# wifi-bt.net
KiCad netlist of a schematic drawn in Altium Designer
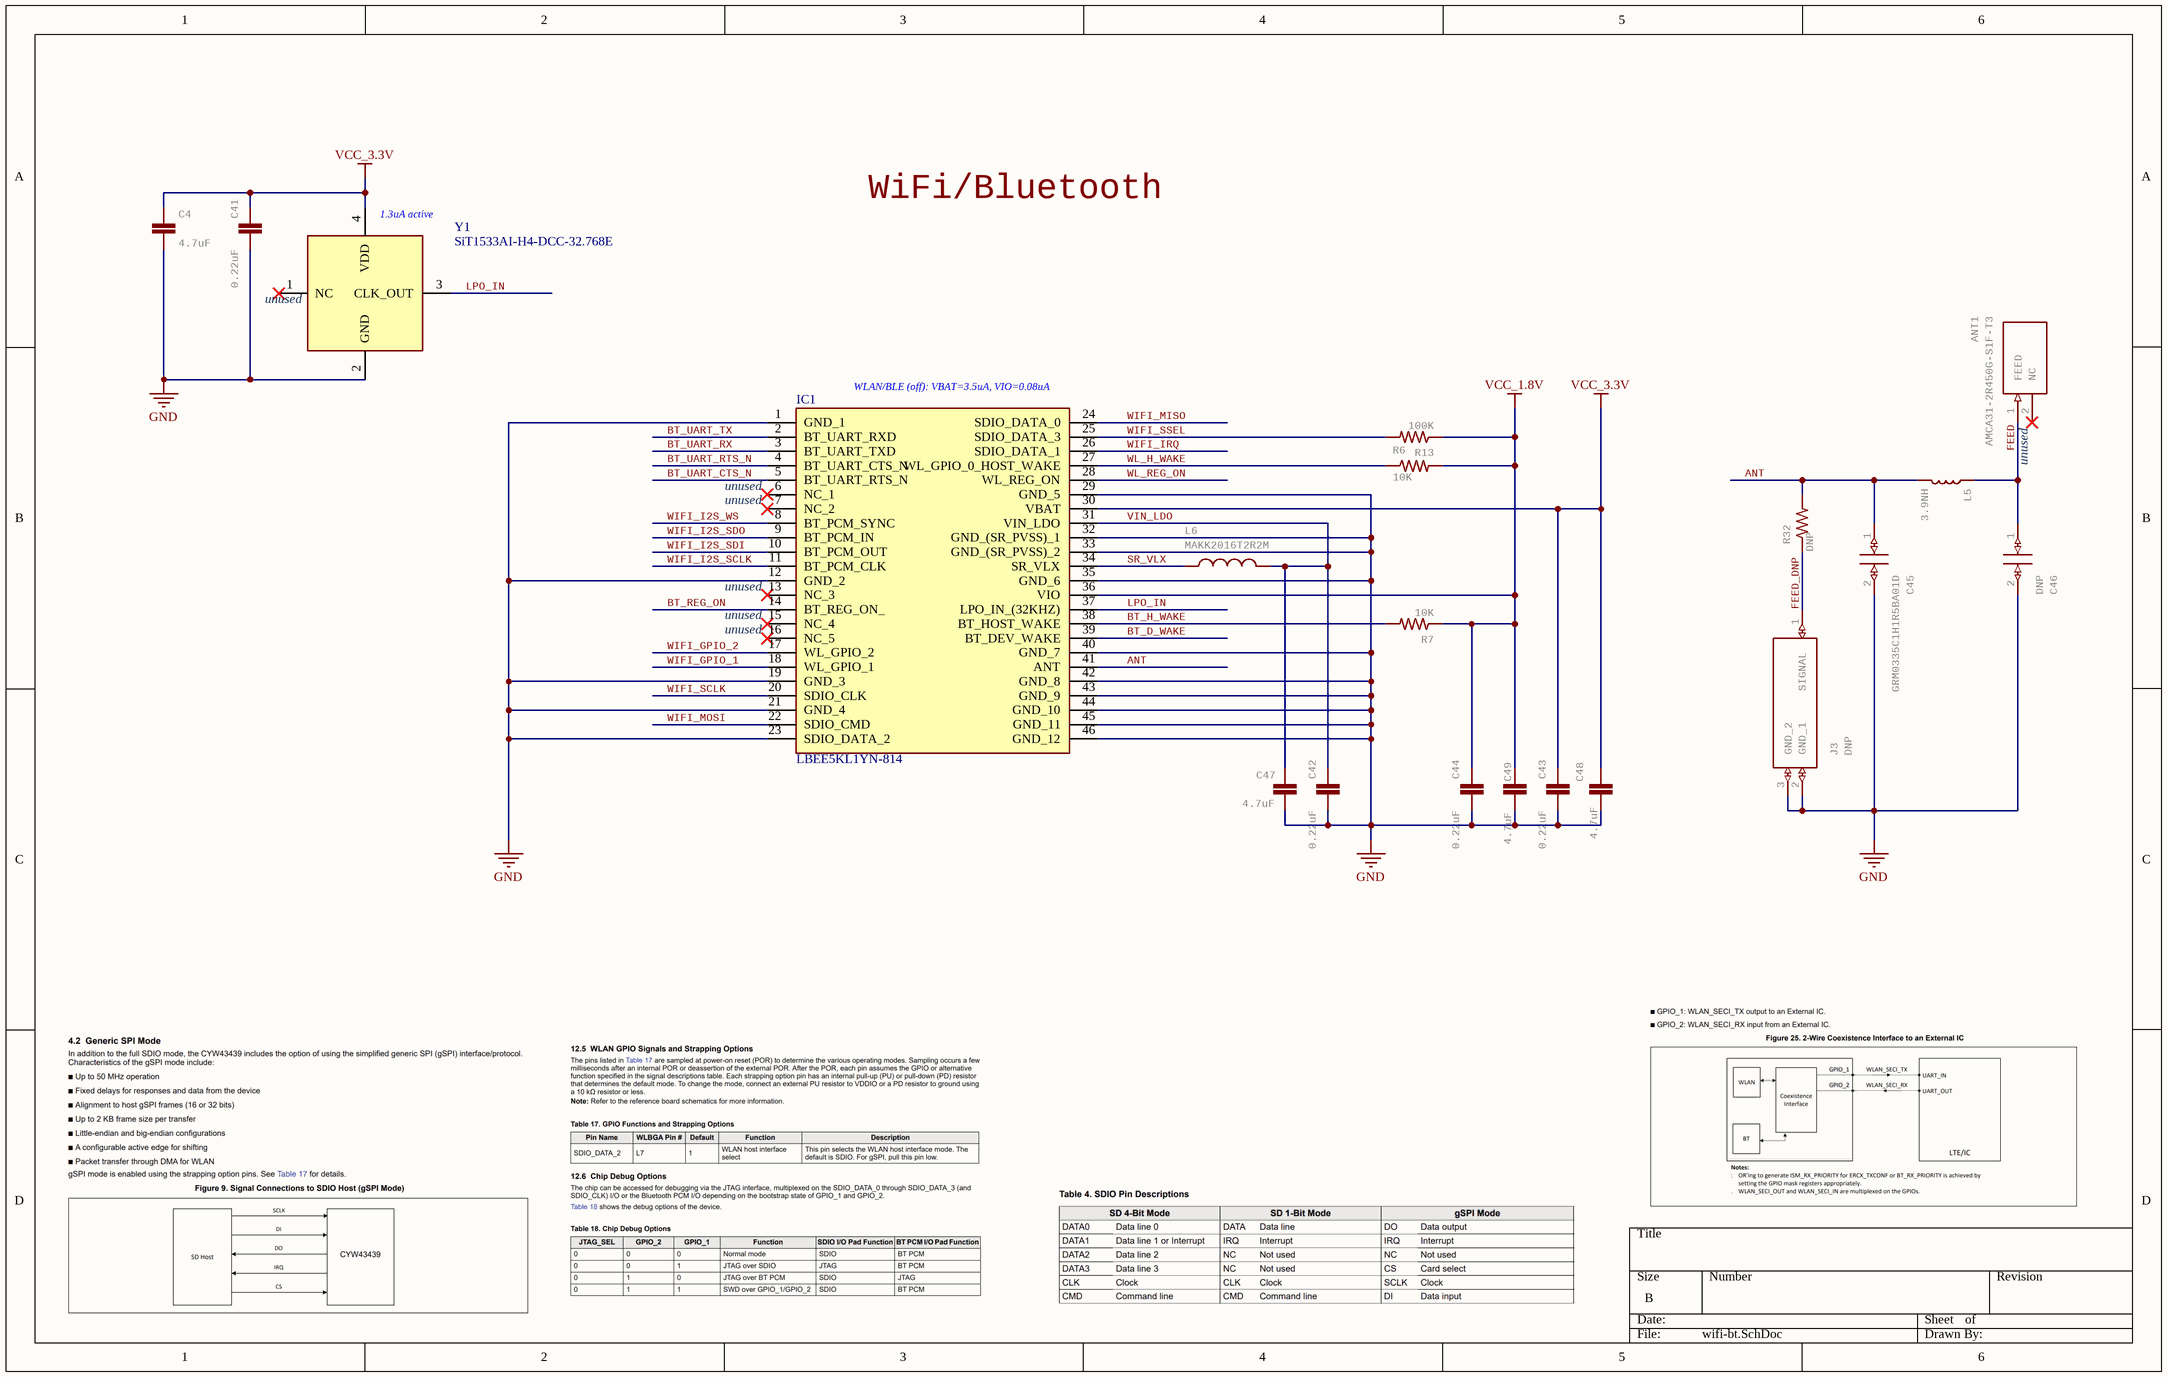
[diagram p0: wifi-bt.SchDoc]

(export (version "E")
  (design (tool "Eeschema 10.0.6"))
  (components
    (comp (ref "ANT1")
      (value "AMCA31-2R450G-S1F-T3")
      (footprint "ANTC3216X140N")
      (description "ABRACON - AMCA31-2R450G-S1F-T3 - ANTENNA, CHIP, 2.45GHZ, 50 OHM, 1206   Source:  Datasheet")
      (fields (field (name "MOUSER_PART_NUMBER") "815-CA312R450GS1FT3"))
      (libsource (lib "openmv-ae3") (part "AMCA31-2R450G-S1F-T3"))
    )
    (comp (ref "C4")
      (value "4.7uF")
      (footprint "0402-CAP")
      (description "CapacitorStandard 0603 ceramic capacitor, and 0.1\" leaded capacitor.")
      (fields (field (name "MPN") "JMK105BBJ475MV-F") (field (name "LIBRARYNAME") "sfe"))
      (libsource (lib "openmv-ae3") (part "CAP0402-CAP"))
    )
    (comp (ref "C41")
      (value "0.22uF")
      (footprint "C0201")
      (description "CAPACITOR, European symbol")
      (fields (field (name "MPN") "GRM033R60J224ME15D"))
      (libsource (lib "openmv-ae3") (part "C-EUC0201"))
    )
    (comp (ref "C42")
      (value "0.22uF")
      (footprint "C0201")
      (description "CAPACITOR, European symbol")
      (fields (field (name "MPN") "GRM033R60J224ME15D"))
      (libsource (lib "openmv-ae3") (part "C-EUC0201"))
    )
    (comp (ref "C43")
      (value "0.22uF")
      (footprint "C0201")
      (description "CAPACITOR, European symbol")
      (fields (field (name "MPN") "GRM033R60J224ME15D"))
      (libsource (lib "openmv-ae3") (part "C-EUC0201"))
    )
    (comp (ref "C44")
      (value "0.22uF")
      (footprint "C0201")
      (description "CAPACITOR, European symbol")
      (fields (field (name "MPN") "GRM033R60J224ME15D"))
      (libsource (lib "openmv-ae3") (part "C-EUC0201"))
    )
    (comp (ref "C45")
      (value "GRM0335C1H1R5BA01D")
      (footprint "CAPC0603X33N")
      (description "Chip Capacitor value 1R5   Source:  Datasheet")
      (fields (field (name "MOUSER_PART_NUMBER") "81-GRM0335C1H1R5BA1D"))
      (libsource (lib "openmv-ae3") (part "GRM0335C1H1R5BA01D"))
    )
    (comp (ref "C46")
      (value "DNP")
      (footprint "C0201-NO-3D")
      (description "Chip Capacitor value 1R5   Source:  Datasheet")
      (fields
        (field (name "MANUFACTURER_PART_NUMBER") "GRM0335C1H1R5BA01D")
        (field (name "MOUSER_PART_NUMBER") "81-GRM0335C1H1R5BA1D")
      )
      (libsource (lib "openmv-ae3") (part "GRM0335C1H1R5BA01D"))
    )
    (comp (ref "C47")
      (value "4.7uF")
      (footprint "0402-CAP")
      (description "CapacitorStandard 0603 ceramic capacitor, and 0.1\" leaded capacitor.")
      (fields (field (name "MPN") "JMK105BBJ475MV-F") (field (name "LIBRARYNAME") "sfe"))
      (libsource (lib "openmv-ae3") (part "CAP0402-CAP"))
    )
    (comp (ref "C48")
      (value "4.7uF")
      (footprint "0402-CAP")
      (description "CapacitorStandard 0603 ceramic capacitor, and 0.1\" leaded capacitor.")
      (fields (field (name "MPN") "JMK105BBJ475MV-F") (field (name "LIBRARYNAME") "sfe"))
      (libsource (lib "openmv-ae3") (part "CAP0402-CAP"))
    )
    (comp (ref "C49")
      (value "4.7uF")
      (footprint "0402-CAP")
      (description "CapacitorStandard 0603 ceramic capacitor, and 0.1\" leaded capacitor.")
      (fields (field (name "MPN") "JMK105BBJ475MV-F") (field (name "LIBRARYNAME") "sfe"))
      (libsource (lib "openmv-ae3") (part "CAP0402-CAP"))
    )
    (comp (ref "IC1")
      (value "LBEE5KL1YN-814")
      (footprint "SamacSys:LBEE5KL1YN814")
      (description "Integrated Circuit")
      (fields (field (name "MOUSER PART NUMBER") "81-LBEE5KL1YN-814"))
      (libsource (lib "openmv-ae3") (part "LBEE5KL1YN-814"))
    )
    (comp (ref "J3")
      (value "DNP")
      (footprint "23370191-NO-3D")
      (description "RF Connectors / Coaxial Connectors MicroCoax receptacle UMCC Gen 1   Source:  Datasheet")
      (fields
        (field (name "MANUFACTURER_PART_NUMBER") "2337019-1")
        (field (name "MOUSER_PART_NUMBER") "571-2337019-1")
      )
      (libsource (lib "openmv-ae3") (part "2337019-1"))
    )
    (comp (ref "L5")
      (value "3.9NH")
      (footprint "0402")
      (fields (field (name "MPN") "L-07C3N9SV6T") (field (name "LIBRARYNAME") "SparkFun-Coils"))
      (libsource (lib "openmv-ae3") (part "INDUCTOR-0402-3.9NH"))
    )
    (comp (ref "L6")
      (value "MAKK2016T2R2M")
      (footprint "INDC2016X100N")
      (description "INDUCTOR, METAL CORE Check availability")
      (fields (field (name "MF") "Taiyo Yuden"))
      (libsource (lib "openmv-ae3") (part "MAKK2016T2R2M"))
    )
    (comp (ref "R6")
      (value "10K")
      (footprint "R0201")
      (fields (field (name "MPN") "RMCF0201FT10K0") (field (name "LIBRARYNAME") "sfe"))
      (libsource (lib "openmv-ae3") (part "RESISTOR0402-RES"))
    )
    (comp (ref "R7")
      (value "10K")
      (footprint "R0201")
      (fields (field (name "MPN") "RMCF0201FT10K0") (field (name "LIBRARYNAME") "sfe"))
      (libsource (lib "openmv-ae3") (part "RESISTOR0402-RES"))
    )
    (comp (ref "R13")
      (value "100K")
      (footprint "R0201")
      (fields (field (name "MPN") "RMCF0201FT100K") (field (name "LIBRARYNAME") "sfe"))
      (libsource (lib "openmv-ae3") (part "RESISTOR0402-RES"))
    )
    (comp (ref "R32")
      (value "DNP")
      (footprint "0402-RES")
      (description "Resistor")
      (fields (field (name "LIBRARYNAME") "sfe"))
      (libsource (lib "openmv-ae3") (part "RESISTOR0402-RES"))
    )
    (comp (ref "Y1")
      (value "SiT1533AI-H4-DCC-32.768E")
      (footprint "SamacSys:SIT1533AIH4AA332768E")
      (description "Crystal or Oscillator")
      (fields (field (name "MOUSER PART NUMBER") "788-1533AIH4DCC32.76"))
      (libsource (lib "openmv-ae3") (part "SIT1533AI-H4-AA3-32.768E"))
    )
  )
  (nets
    (net (code "1") (name "/ANT") (class "Default")
      (node (ref "C45") (pin "1") (pinfunction "1_1") (pintype "bidirectional"))
      (node (ref "IC1") (pin "41") (pinfunction "ANT_41") (pintype "passive"))
      (node (ref "L5") (pin "2") (pinfunction "2_2") (pintype "passive"))
      (node (ref "R32") (pin "2") (pinfunction "2_2") (pintype "passive"))
    )
    (net (code "2") (name "/BT_D_WAKE") (class "Default")
      (node (ref "IC1") (pin "39") (pinfunction "BT_DEV_WAKE_39") (pintype "passive"))
    )
    (net (code "3") (name "/BT_H_WAKE") (class "Default")
      (node (ref "IC1") (pin "38") (pinfunction "BT_HOST_WAKE_38") (pintype "passive"))
      (node (ref "R7") (pin "2") (pinfunction "2_2") (pintype "passive"))
    )
    (net (code "4") (name "/BT_REG_ON") (class "Default")
      (node (ref "IC1") (pin "14") (pinfunction "BT_REG_ON__14") (pintype "passive"))
    )
    (net (code "5") (name "/BT_UART_CTS_N") (class "Default")
      (node (ref "IC1") (pin "5") (pinfunction "BT_UART_RTS_N_5") (pintype "passive"))
    )
    (net (code "6") (name "/BT_UART_RTS_N") (class "Default")
      (node (ref "IC1") (pin "4") (pinfunction "BT_UART_CTS_N_4") (pintype "passive"))
    )
    (net (code "7") (name "/BT_UART_RX") (class "Default")
      (node (ref "IC1") (pin "3") (pinfunction "BT_UART_TXD_3") (pintype "passive"))
    )
    (net (code "8") (name "/BT_UART_TX") (class "Default")
      (node (ref "IC1") (pin "2") (pinfunction "BT_UART_RXD_2") (pintype "passive"))
    )
    (net (code "9") (name "/FEED") (class "Default")
      (node (ref "ANT1") (pin "1") (pinfunction "FEED_1") (pintype "input"))
      (node (ref "C46") (pin "1") (pinfunction "1_1") (pintype "bidirectional"))
      (node (ref "L5") (pin "1") (pinfunction "1_1") (pintype "passive"))
    )
    (net (code "10") (name "/FEED_DNP") (class "Default")
      (node (ref "J3") (pin "1") (pinfunction "SIGNAL_1") (pintype "bidirectional"))
      (node (ref "R32") (pin "1") (pinfunction "1_1") (pintype "passive"))
    )
    (net (code "11") (name "/LPO_IN") (class "Default")
      (node (ref "IC1") (pin "37") (pinfunction "LPO_IN_(32KHZ)_37") (pintype "passive"))
      (node (ref "Y1") (pin "3") (pinfunction "CLK_OUT_3") (pintype "passive"))
    )
    (net (code "12") (name "/SR_VLX") (class "Default")
      (node (ref "IC1") (pin "34") (pinfunction "SR_VLX_34") (pintype "passive"))
      (node (ref "L6") (pin "1") (pinfunction "1_1") (pintype "passive"))
    )
    (net (code "13") (name "/VIN_LDO") (class "Default")
      (node (ref "C42") (pin "1") (pinfunction "1_1") (pintype "passive"))
      (node (ref "C47") (pin "2") (pinfunction "2_2") (pintype "passive"))
      (node (ref "IC1") (pin "31") (pinfunction "VIN_LDO_31") (pintype "passive"))
      (node (ref "L6") (pin "2") (pinfunction "2_2") (pintype "passive"))
    )
    (net (code "14") (name "/WIFI_GPIO_1") (class "Default")
      (node (ref "IC1") (pin "18") (pinfunction "WL_GPIO_1_18") (pintype "passive"))
    )
    (net (code "15") (name "/WIFI_GPIO_2") (class "Default")
      (node (ref "IC1") (pin "17") (pinfunction "WL_GPIO_2_17") (pintype "passive"))
    )
    (net (code "16") (name "/WIFI_I2S_SCLK") (class "Default")
      (node (ref "IC1") (pin "11") (pinfunction "BT_PCM_CLK_11") (pintype "passive"))
    )
    (net (code "17") (name "/WIFI_I2S_SDI") (class "Default")
      (node (ref "IC1") (pin "10") (pinfunction "BT_PCM_OUT_10") (pintype "passive"))
    )
    (net (code "18") (name "/WIFI_I2S_SDO") (class "Default")
      (node (ref "IC1") (pin "9") (pinfunction "BT_PCM_IN_9") (pintype "passive"))
    )
    (net (code "19") (name "/WIFI_I2S_WS") (class "Default")
      (node (ref "IC1") (pin "8") (pinfunction "BT_PCM_SYNC_8") (pintype "passive"))
    )
    (net (code "20") (name "/WIFI_IRQ") (class "Default")
      (node (ref "IC1") (pin "26") (pinfunction "SDIO_DATA_1_26") (pintype "passive"))
    )
    (net (code "21") (name "/WIFI_MISO") (class "Default")
      (node (ref "IC1") (pin "24") (pinfunction "SDIO_DATA_0_24") (pintype "passive"))
    )
    (net (code "22") (name "/WIFI_MOSI") (class "Default")
      (node (ref "IC1") (pin "22") (pinfunction "SDIO_CMD_22") (pintype "passive"))
    )
    (net (code "23") (name "/WIFI_SCLK") (class "Default")
      (node (ref "IC1") (pin "20") (pinfunction "SDIO_CLK_20") (pintype "passive"))
    )
    (net (code "24") (name "/WIFI_SSEL") (class "Default")
      (node (ref "IC1") (pin "25") (pinfunction "SDIO_DATA_3_25") (pintype "passive"))
      (node (ref "R13") (pin "2") (pinfunction "2_2") (pintype "passive"))
    )
    (net (code "25") (name "/WL_H_WAKE") (class "Default")
      (node (ref "IC1") (pin "27") (pinfunction "WL_GPIO_0_HOST_WAKE_27") (pintype "passive"))
      (node (ref "R6") (pin "1") (pinfunction "1_1") (pintype "passive"))
    )
    (net (code "26") (name "/WL_REG_ON") (class "Default")
      (node (ref "IC1") (pin "28") (pinfunction "WL_REG_ON_28") (pintype "passive"))
    )
    (net (code "27") (name "GND") (class "Default")
      (node (ref "C4") (pin "1") (pinfunction "1_1") (pintype "passive"))
      (node (ref "C41") (pin "2") (pinfunction "2_2") (pintype "passive"))
      (node (ref "C42") (pin "2") (pinfunction "2_2") (pintype "passive"))
      (node (ref "C43") (pin "2") (pinfunction "2_2") (pintype "passive"))
      (node (ref "C44") (pin "2") (pinfunction "2_2") (pintype "passive"))
      (node (ref "C45") (pin "2") (pinfunction "2_2") (pintype "bidirectional"))
      (node (ref "C46") (pin "2") (pinfunction "2_2") (pintype "bidirectional"))
      (node (ref "C47") (pin "1") (pinfunction "1_1") (pintype "passive"))
      (node (ref "C48") (pin "1") (pinfunction "1_1") (pintype "passive"))
      (node (ref "C49") (pin "1") (pinfunction "1_1") (pintype "passive"))
      (node (ref "IC1") (pin "1") (pinfunction "GND_1_1") (pintype "passive"))
      (node (ref "IC1") (pin "12") (pinfunction "GND_2_12") (pintype "passive"))
      (node (ref "IC1") (pin "19") (pinfunction "GND_3_19") (pintype "passive"))
      (node (ref "IC1") (pin "21") (pinfunction "GND_4_21") (pintype "passive"))
      (node (ref "IC1") (pin "23") (pinfunction "SDIO_DATA_2_23") (pintype "passive"))
      (node (ref "IC1") (pin "29") (pinfunction "GND_5_29") (pintype "passive"))
      (node (ref "IC1") (pin "32") (pinfunction "GND_(SR_PVSS)_1_32") (pintype "passive"))
      (node (ref "IC1") (pin "33") (pinfunction "GND_(SR_PVSS)_2_33") (pintype "passive"))
      (node (ref "IC1") (pin "35") (pinfunction "GND_6_35") (pintype "passive"))
      (node (ref "IC1") (pin "40") (pinfunction "GND_7_40") (pintype "passive"))
      (node (ref "IC1") (pin "42") (pinfunction "GND_8_42") (pintype "passive"))
      (node (ref "IC1") (pin "43") (pinfunction "GND_9_43") (pintype "passive"))
      (node (ref "IC1") (pin "44") (pinfunction "GND_10_44") (pintype "passive"))
      (node (ref "IC1") (pin "45") (pinfunction "GND_11_45") (pintype "passive"))
      (node (ref "IC1") (pin "46") (pinfunction "GND_12_46") (pintype "passive"))
      (node (ref "J3") (pin "2") (pinfunction "GND_1_2") (pintype "bidirectional"))
      (node (ref "J3") (pin "3") (pinfunction "GND_2_3") (pintype "bidirectional"))
      (node (ref "Y1") (pin "2") (pinfunction "GND_2") (pintype "passive"))
    )
    (net (code "28") (name "VCC_1.8V") (class "Default")
      (node (ref "C44") (pin "1") (pinfunction "1_1") (pintype "passive"))
      (node (ref "C49") (pin "2") (pinfunction "2_2") (pintype "passive"))
      (node (ref "IC1") (pin "36") (pinfunction "VIO_36") (pintype "passive"))
      (node (ref "R13") (pin "1") (pinfunction "1_1") (pintype "passive"))
      (node (ref "R6") (pin "2") (pinfunction "2_2") (pintype "passive"))
      (node (ref "R7") (pin "1") (pinfunction "1_1") (pintype "passive"))
    )
    (net (code "29") (name "VCC_3.3V") (class "Default")
      (node (ref "C4") (pin "2") (pinfunction "2_2") (pintype "passive"))
      (node (ref "C41") (pin "1") (pinfunction "1_1") (pintype "passive"))
      (node (ref "C43") (pin "1") (pinfunction "1_1") (pintype "passive"))
      (node (ref "C48") (pin "2") (pinfunction "2_2") (pintype "passive"))
      (node (ref "IC1") (pin "30") (pinfunction "VBAT_30") (pintype "passive"))
      (node (ref "Y1") (pin "4") (pinfunction "VDD_4") (pintype "passive"))
    )
    (net (code "30") (name "unconnected-(ANT1-NC-Pad2)") (class "Default")
      (node (ref "ANT1") (pin "2") (pinfunction "NC_2") (pintype "passive+no_connect"))
    )
    (net (code "31") (name "unconnected-(IC1-NC_1-Pad6)") (class "Default")
      (node (ref "IC1") (pin "6") (pinfunction "NC_1_6") (pintype "passive+no_connect"))
    )
    (net (code "32") (name "unconnected-(IC1-NC_2-Pad7)") (class "Default")
      (node (ref "IC1") (pin "7") (pinfunction "NC_2_7") (pintype "passive+no_connect"))
    )
    (net (code "33") (name "unconnected-(IC1-NC_3-Pad13)") (class "Default")
      (node (ref "IC1") (pin "13") (pinfunction "NC_3_13") (pintype "passive+no_connect"))
    )
    (net (code "34") (name "unconnected-(IC1-NC_4-Pad15)") (class "Default")
      (node (ref "IC1") (pin "15") (pinfunction "NC_4_15") (pintype "passive+no_connect"))
    )
    (net (code "35") (name "unconnected-(IC1-NC_5-Pad16)") (class "Default")
      (node (ref "IC1") (pin "16") (pinfunction "NC_5_16") (pintype "passive+no_connect"))
    )
    (net (code "36") (name "unconnected-(Y1-NC-Pad1)") (class "Default")
      (node (ref "Y1") (pin "1") (pinfunction "NC_1") (pintype "passive+no_connect"))
    )
  )
)
